# KickerBoost.net
KiCad netlist of a schematic drawn in EAGLE
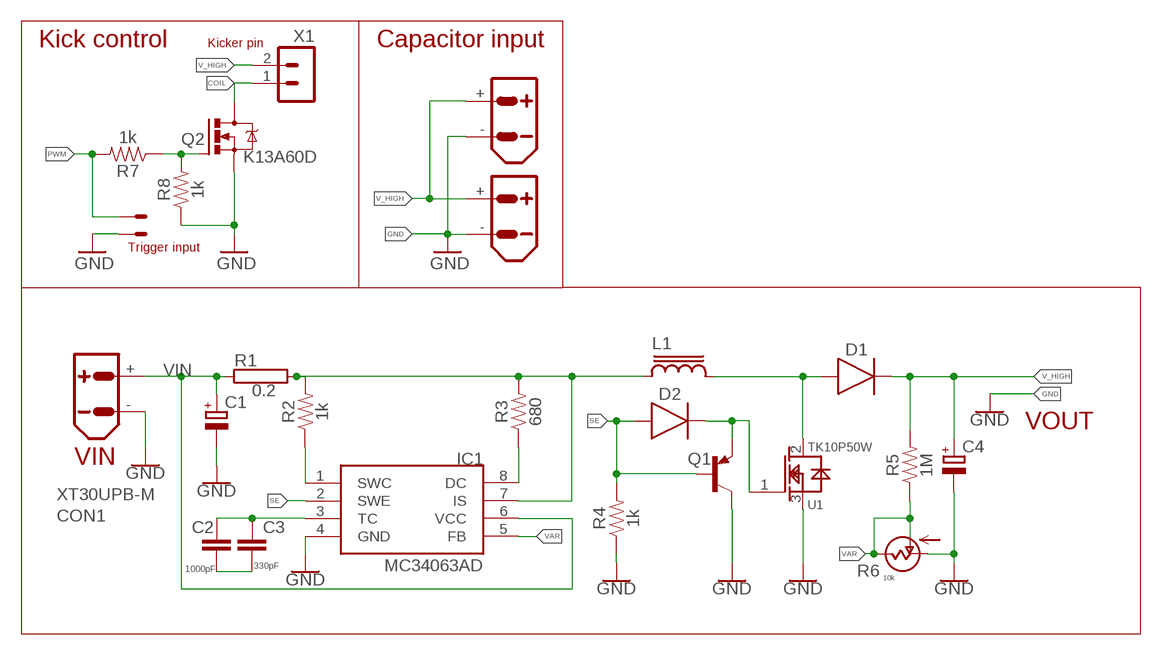
[diagram p0: schematic, sheet 1]

(export (version "E")
  (design (tool "Eeschema 10.0.6"))
  (components
    (comp (ref "C1")
      (value "CPOL-EUE5-8.5")
      (footprint "eagle-import:E5-8,5")
      (libsource (lib "eagle-import") (part "CPOL-EUE5-8.5"))
    )
    (comp (ref "C2")
      (value "1000pF")
      (footprint "eagle-import:0603")
      (libsource (lib "eagle-import") (part "0.1UF-0603-25V-(+80/-20%)"))
    )
    (comp (ref "C3")
      (value "330pF")
      (footprint "eagle-import:0603")
      (libsource (lib "eagle-import") (part "0.1UF-0603-25V-(+80/-20%)"))
    )
    (comp (ref "C4")
      (value "CPOL-EUE5-10.5")
      (footprint "eagle-import:E5-10,5")
      (libsource (lib "eagle-import") (part "CPOL-EUE5-10.5"))
    )
    (comp (ref "CON1")
      (value "XT30UPB-M")
      (footprint "eagle-import:XT30UPB-M")
      (libsource (lib "eagle-import") (part "XT30UPB-M"))
    )
    (comp (ref "CON4")
      (value "XT30UPB-M")
      (footprint "eagle-import:XT30UPB-M")
      (libsource (lib "eagle-import") (part "XT30UPB-M"))
    )
    (comp (ref "CON5")
      (value "XT30UPB-M")
      (footprint "eagle-import:XT30UPB-M")
      (libsource (lib "eagle-import") (part "XT30UPB-M"))
    )
    (comp (ref "D1")
      (value "MRA4007T3G")
      (footprint "eagle-import:DIOM5226X290N")
      (fields (field (name "MANUFACTURER") "ON Semiconductor"))
      (libsource (lib "eagle-import") (part "DIODE__SMAMRA4007T3G"))
    )
    (comp (ref "D2")
      (value "MRA4007T3G")
      (footprint "eagle-import:DIOM5226X290N")
      (fields (field (name "MANUFACTURER") "ON Semiconductor"))
      (libsource (lib "eagle-import") (part "DIODE__SMAMRA4007T3G"))
    )
    (comp (ref "IC1")
      (value "MC34063AD")
      (footprint "eagle-import:SOIC8")
      (libsource (lib "eagle-import") (part "MC34063AD"))
    )
    (comp (ref "L1")
      (value "CDRH127/LD")
      (footprint "eagle-import:CDRH127_LD")
      (libsource (lib "eagle-import") (part "CDRH127/LD"))
    )
    (comp (ref "Q1")
      (value "BCX71SMD")
      (footprint "eagle-import:SOT23")
      (libsource (lib "eagle-import") (part "BCX71SMD"))
    )
    (comp (ref "Q2")
      (value "K13A60D")
      (footprint "eagle-import:TO220BV")
      (libsource (lib "eagle-import") (part "K13A60D"))
    )
    (comp (ref "R1")
      (value "0.2")
      (footprint "eagle-import:KH208-8")
      (libsource (lib "eagle-import") (part "RKH208-8"))
    )
    (comp (ref "R2")
      (value "1k")
      (footprint "eagle-import:0603")
      (libsource (lib "eagle-import") (part "1KOHM-0603-1/10W-1%"))
    )
    (comp (ref "R3")
      (value "680")
      (footprint "eagle-import:0603")
      (libsource (lib "eagle-import") (part "1KOHM-0603-1/10W-1%"))
    )
    (comp (ref "R4")
      (value "1k")
      (footprint "eagle-import:0603")
      (libsource (lib "eagle-import") (part "1KOHM-0603-1/10W-1%"))
    )
    (comp (ref "R5")
      (value "1M")
      (footprint "eagle-import:0603")
      (libsource (lib "eagle-import") (part "1KOHM-0603-1/10W-1%"))
    )
    (comp (ref "R6")
      (value "10K")
      (footprint "eagle-import:S64W")
      (libsource (lib "eagle-import") (part "POTTRS64W"))
    )
    (comp (ref "R7")
      (value "1k")
      (footprint "eagle-import:0603")
      (libsource (lib "eagle-import") (part "1KOHM-0603-1/10W-1%"))
    )
    (comp (ref "R8")
      (value "1k")
      (footprint "eagle-import:0603")
      (libsource (lib "eagle-import") (part "1KOHM-0603-1/10W-1%"))
    )
    (comp (ref "U1")
      (value "TK10P50W")
      (footprint "eagle-import:TK10P50W")
      (libsource (lib "eagle-import") (part "TK10P50W"))
    )
    (comp (ref "X1")
      (value "VH2")
      (footprint "eagle-import:B2P-VH-FB-B")
      (libsource (lib "eagle-import") (part "B2P-VH-FB-B"))
    )
    (comp (ref "X2")
      (value "HX2")
      (footprint "eagle-import:JST-XH-02-PACKAGE-LONG-PAD")
      (libsource (lib "eagle-import") (part "JST-XH-02-PIN-LONG-PAD"))
    )
  )
  (nets
    (net (code "1") (name "/VIN") (class "Default")
      (node (ref "C1") (pin "+") (pinfunction "+_+") (pintype "passive"))
      (node (ref "CON1") (pin "+") (pinfunction "+_+") (pintype "power_in"))
      (node (ref "IC1") (pin "6") (pinfunction "VCC_6") (pintype "passive"))
      (node (ref "R1") (pin "1") (pinfunction "1_1") (pintype "passive"))
    )
    (net (code "2") (name "COIL") (class "Default")
      (node (ref "Q2") (pin "D") (pinfunction "D_D") (pintype "passive"))
      (node (ref "X1") (pin "1") (pinfunction "1_1") (pintype "passive"))
    )
    (net (code "3") (name "GND") (class "Default")
      (node (ref "C1") (pin "-") (pinfunction "-_-") (pintype "passive"))
      (node (ref "C4") (pin "-") (pinfunction "-_-") (pintype "passive"))
      (node (ref "CON1") (pin "-") (pinfunction "-_-") (pintype "power_in"))
      (node (ref "CON4") (pin "-") (pinfunction "-_-") (pintype "power_in"))
      (node (ref "CON5") (pin "-") (pinfunction "-_-") (pintype "power_in"))
      (node (ref "IC1") (pin "4") (pinfunction "GND_4") (pintype "passive"))
      (node (ref "Q1") (pin "3") (pinfunction "C_3") (pintype "passive"))
      (node (ref "Q2") (pin "S") (pinfunction "S_S") (pintype "passive"))
      (node (ref "R4") (pin "1") (pinfunction "1_1") (pintype "passive"))
      (node (ref "R6") (pin "A") (pinfunction "VDD_A") (pintype "passive"))
      (node (ref "R8") (pin "1") (pinfunction "1_1") (pintype "passive"))
      (node (ref "U1") (pin "3") (pinfunction "SOURCE_3") (pintype "input"))
      (node (ref "X2") (pin "2") (pinfunction "S_2") (pintype "passive"))
    )
    (net (code "4") (name "Net-(C2-Pad2)") (class "Default")
      (node (ref "C2") (pin "2") (pinfunction "2_2") (pintype "passive"))
      (node (ref "C3") (pin "2") (pinfunction "2_2") (pintype "passive"))
    )
    (net (code "5") (name "Net-(D1-A)") (class "Default")
      (node (ref "D1") (pin "2") (pinfunction "A_2") (pintype "passive"))
      (node (ref "L1") (pin "2") (pinfunction "2_2") (pintype "passive"))
      (node (ref "U1") (pin "2") (pinfunction "DRAIN_2") (pintype "output"))
    )
    (net (code "6") (name "Net-(D2-C)") (class "Default")
      (node (ref "D2") (pin "1") (pinfunction "C_1") (pintype "passive"))
      (node (ref "Q1") (pin "2") (pinfunction "E_2") (pintype "passive"))
      (node (ref "U1") (pin "1") (pinfunction "GATE_1") (pintype "input"))
    )
    (net (code "7") (name "Net-(IC1-DC)") (class "Default")
      (node (ref "IC1") (pin "8") (pinfunction "DC_8") (pintype "passive"))
      (node (ref "R3") (pin "1") (pinfunction "1_1") (pintype "passive"))
    )
    (net (code "8") (name "Net-(IC1-IS)") (class "Default")
      (node (ref "IC1") (pin "7") (pinfunction "IS_7") (pintype "passive"))
      (node (ref "L1") (pin "1") (pinfunction "1_1") (pintype "passive"))
      (node (ref "R1") (pin "2") (pinfunction "2_2") (pintype "passive"))
      (node (ref "R2") (pin "2") (pinfunction "2_2") (pintype "passive"))
      (node (ref "R3") (pin "2") (pinfunction "2_2") (pintype "passive"))
    )
    (net (code "9") (name "Net-(IC1-SWC)") (class "Default")
      (node (ref "IC1") (pin "1") (pinfunction "SWC_1") (pintype "passive"))
      (node (ref "R2") (pin "1") (pinfunction "1_1") (pintype "passive"))
    )
    (net (code "10") (name "Net-(IC1-TC)") (class "Default")
      (node (ref "C2") (pin "1") (pinfunction "1_1") (pintype "passive"))
      (node (ref "C3") (pin "1") (pinfunction "1_1") (pintype "passive"))
      (node (ref "IC1") (pin "3") (pinfunction "TC_3") (pintype "passive"))
    )
    (net (code "11") (name "Net-(Q2-PadG)") (class "Default")
      (node (ref "Q2") (pin "G") (pinfunction "G_G") (pintype "passive"))
      (node (ref "R7") (pin "1") (pinfunction "1_1") (pintype "passive"))
      (node (ref "R8") (pin "2") (pinfunction "2_2") (pintype "passive"))
    )
    (net (code "12") (name "PWM") (class "Default")
      (node (ref "R7") (pin "2") (pinfunction "2_2") (pintype "passive"))
      (node (ref "X2") (pin "1") (pinfunction "S_1") (pintype "passive"))
    )
    (net (code "13") (name "SE") (class "Default")
      (node (ref "D2") (pin "2") (pinfunction "A_2") (pintype "passive"))
      (node (ref "IC1") (pin "2") (pinfunction "SWE_2") (pintype "passive"))
      (node (ref "Q1") (pin "1") (pinfunction "B_1") (pintype "passive"))
      (node (ref "R4") (pin "2") (pinfunction "2_2") (pintype "passive"))
    )
    (net (code "14") (name "VAR") (class "Default")
      (node (ref "IC1") (pin "5") (pinfunction "FB_5") (pintype "passive"))
      (node (ref "R5") (pin "1") (pinfunction "1_1") (pintype "passive"))
      (node (ref "R6") (pin "E") (pinfunction "VSS_E") (pintype "passive"))
      (node (ref "R6") (pin "S") (pinfunction "OUT_S") (pintype "passive"))
    )
    (net (code "15") (name "V_HIGH") (class "Default")
      (node (ref "C4") (pin "+") (pinfunction "+_+") (pintype "passive"))
      (node (ref "CON4") (pin "+") (pinfunction "+_+") (pintype "power_in"))
      (node (ref "CON5") (pin "+") (pinfunction "+_+") (pintype "power_in"))
      (node (ref "D1") (pin "1") (pinfunction "C_1") (pintype "passive"))
      (node (ref "R5") (pin "2") (pinfunction "2_2") (pintype "passive"))
      (node (ref "X1") (pin "2") (pinfunction "2_2") (pintype "passive"))
    )
  )
)
